# Cartev1.net
KiCad netlist of a schematic drawn in EAGLE
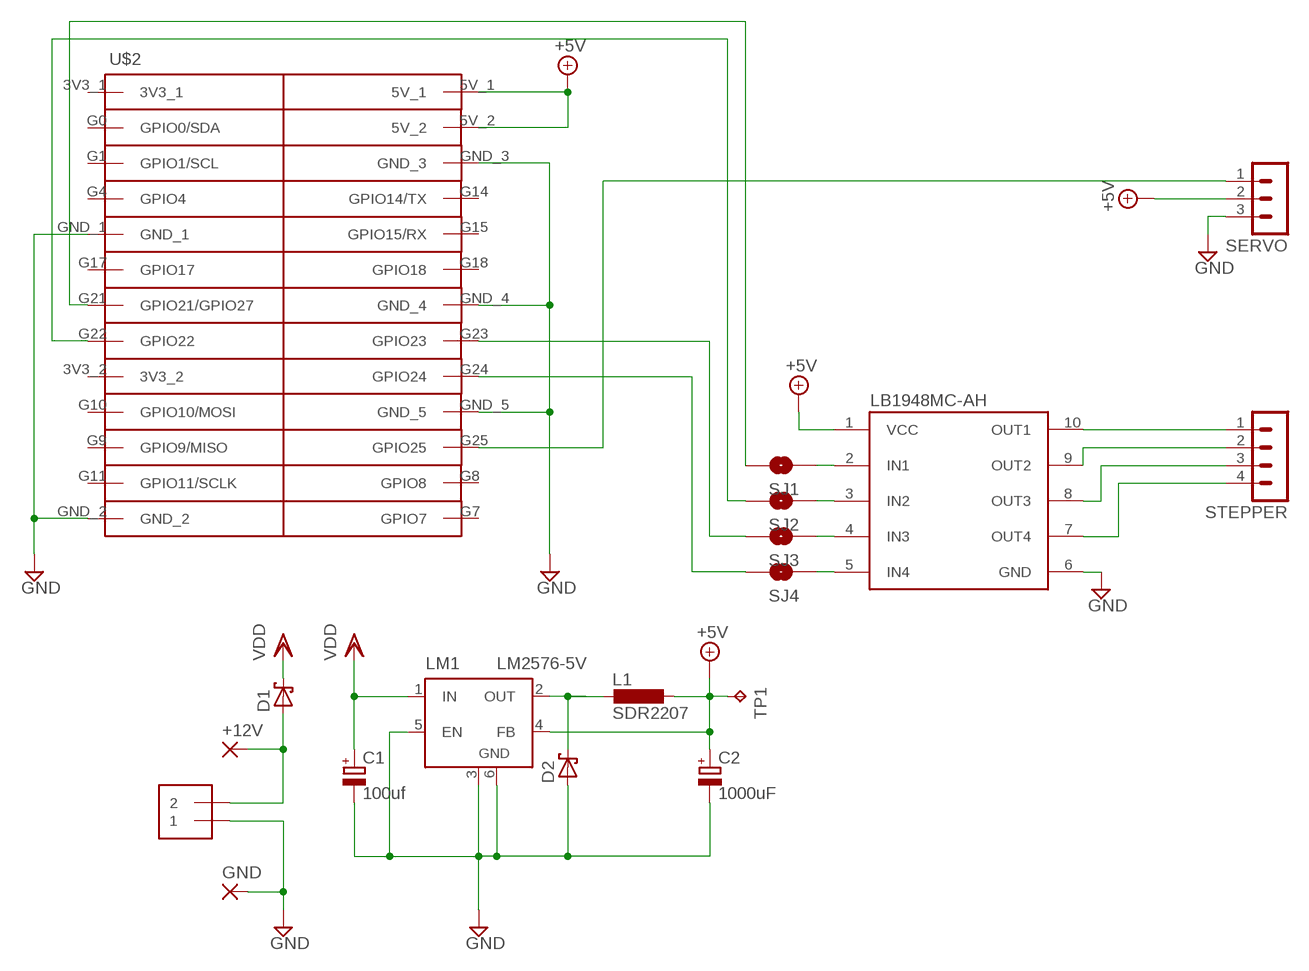
[diagram p0: schematic, sheet 1]

(export (version "E")
  (design (tool "Eeschema 10.0.6"))
  (components
    (comp (ref "+12V")
      (value "3,81/1,4")
      (footprint "eagle-import:3,81_1,4")
      (libsource (lib "eagle-import") (part "3,81/1,4"))
    )
    (comp (ref "C1")
      (value "100uf")
      (footprint "eagle-import:PANASONIC_E")
      (libsource (lib "eagle-import") (part "CPOL-EUE"))
    )
    (comp (ref "C2")
      (value "1000uF")
      (footprint "eagle-import:PANASONIC_G")
      (libsource (lib "eagle-import") (part "CPOL-EUG"))
    )
    (comp (ref "D1")
      (value "SCHOTTKY-DIODESMC")
      (footprint "eagle-import:SMC")
      (libsource (lib "eagle-import") (part "SCHOTTKY-DIODESMC"))
    )
    (comp (ref "D2")
      (value "SCHOTTKY-DIODESMC")
      (footprint "eagle-import:SMC")
      (libsource (lib "eagle-import") (part "SCHOTTKY-DIODESMC"))
    )
    (comp (ref "GND")
      (value "3,81/1,4")
      (footprint "eagle-import:3,81_1,4")
      (libsource (lib "eagle-import") (part "3,81/1,4"))
    )
    (comp (ref "J1")
      (value "1X2-3.5MM")
      (footprint "eagle-import:3.5MMTERM")
      (libsource (lib "eagle-import") (part "1X2-3.5MM"))
    )
    (comp (ref "L1")
      (value "SDR2207")
      (footprint "eagle-import:SM")
      (libsource (lib "eagle-import") (part "SDR2207"))
    )
    (comp (ref "LB1948MC-AH")
      (value "LB1948MC-AH")
      (footprint "eagle-import:SOIC-10")
      (libsource (lib "eagle-import") (part "LB1948MC-AH"))
    )
    (comp (ref "LM1")
      (value "LM2576-5V")
      (footprint "eagle-import:TO263-5")
      (libsource (lib "eagle-import") (part "LM2596S"))
    )
    (comp (ref "SERVO")
      (value "MA03-1")
      (footprint "eagle-import:MA03-1")
      (libsource (lib "eagle-import") (part "MA03-1"))
    )
    (comp (ref "SJ1")
      (value "SOLDERJUMPERTRACE")
      (footprint "eagle-import:SJ_2S-TRACE")
      (libsource (lib "eagle-import") (part "SOLDERJUMPERTRACE"))
    )
    (comp (ref "SJ2")
      (value "SOLDERJUMPERTRACE")
      (footprint "eagle-import:SJ_2S-TRACE")
      (libsource (lib "eagle-import") (part "SOLDERJUMPERTRACE"))
    )
    (comp (ref "SJ3")
      (value "SOLDERJUMPERTRACE")
      (footprint "eagle-import:SJ_2S-TRACE")
      (libsource (lib "eagle-import") (part "SOLDERJUMPERTRACE"))
    )
    (comp (ref "SJ4")
      (value "SOLDERJUMPERTRACE")
      (footprint "eagle-import:SJ_2S-TRACE")
      (libsource (lib "eagle-import") (part "SOLDERJUMPERTRACE"))
    )
    (comp (ref "STEPPER")
      (value "MA04-1")
      (footprint "eagle-import:MA04-1")
      (libsource (lib "eagle-import") (part "MA04-1"))
    )
    (comp (ref "TP1")
      (value "TPTP10SQ")
      (footprint "eagle-import:TP10SQ")
      (libsource (lib "eagle-import") (part "TPTP10SQ"))
    )
    (comp (ref "U$2")
      (value "CONNECTEUR_RPI")
      (footprint "eagle-import:26PIN")
      (libsource (lib "eagle-import") (part "CONNECTEUR_RPI"))
    )
  )
  (nets
    (net (code "1") (name "+5V") (class "Default")
      (node (ref "C2") (pin "+") (pinfunction "+_+") (pintype "passive"))
      (node (ref "L1") (pin "P$2") (pinfunction "2_P$2") (pintype "passive"))
      (node (ref "LB1948MC-AH") (pin "1") (pinfunction "VCC_1") (pintype "bidirectional"))
      (node (ref "LM1") (pin "4") (pinfunction "FB_4") (pintype "input"))
      (node (ref "SERVO") (pin "2") (pinfunction "2_2") (pintype "passive"))
      (node (ref "TP1") (pin "TP") (pinfunction "TP_TP") (pintype "input"))
      (node (ref "U$2") (pin "5V_1") (pinfunction "5V_1_5V_1") (pintype "bidirectional"))
      (node (ref "U$2") (pin "5V_2") (pinfunction "5V_2_5V_2") (pintype "bidirectional"))
    )
    (net (code "2") (name "GND") (class "Default")
      (node (ref "C1") (pin "-") (pinfunction "-_-") (pintype "passive"))
      (node (ref "C2") (pin "-") (pinfunction "-_-") (pintype "passive"))
      (node (ref "D2") (pin "A") (pinfunction "A_A") (pintype "passive"))
      (node (ref "GND") (pin "1") (pinfunction "P_1") (pintype "passive"))
      (node (ref "J1") (pin "1") (pinfunction "1_1") (pintype "passive"))
      (node (ref "LB1948MC-AH") (pin "6") (pinfunction "GND_6") (pintype "bidirectional"))
      (node (ref "LM1") (pin "3") (pinfunction "GND_3") (pintype "power_in"))
      (node (ref "LM1") (pin "5") (pinfunction "EN_5") (pintype "input"))
      (node (ref "LM1") (pin "6") (pinfunction "GND_6") (pintype "power_in"))
      (node (ref "SERVO") (pin "3") (pinfunction "3_3") (pintype "passive"))
      (node (ref "U$2") (pin "GND_1") (pinfunction "GND_1_GND_1") (pintype "bidirectional"))
      (node (ref "U$2") (pin "GND_2") (pinfunction "GND_2_GND_2") (pintype "bidirectional"))
      (node (ref "U$2") (pin "GND_3") (pinfunction "GND_3_GND_3") (pintype "bidirectional"))
      (node (ref "U$2") (pin "GND_4") (pinfunction "GND_4_GND_4") (pintype "bidirectional"))
      (node (ref "U$2") (pin "GND_5") (pinfunction "GND_5_GND_5") (pintype "bidirectional"))
    )
    (net (code "3") (name "Net-(+12V-P)") (class "Default")
      (node (ref "+12V") (pin "1") (pinfunction "P_1") (pintype "passive"))
      (node (ref "D1") (pin "A") (pinfunction "A_A") (pintype "passive"))
      (node (ref "J1") (pin "2") (pinfunction "2_2") (pintype "passive"))
    )
    (net (code "4") (name "Net-(L1-1)") (class "Default")
      (node (ref "D2") (pin "C") (pinfunction "C_C") (pintype "passive"))
      (node (ref "L1") (pin "P$1") (pinfunction "1_P$1") (pintype "passive"))
      (node (ref "LM1") (pin "2") (pinfunction "OUT_2") (pintype "output"))
    )
    (net (code "5") (name "Net-(LB1948MC-AH-IN1)") (class "Default")
      (node (ref "LB1948MC-AH") (pin "2") (pinfunction "IN1_2") (pintype "bidirectional"))
      (node (ref "SJ1") (pin "1") (pinfunction "1_1") (pintype "passive"))
    )
    (net (code "6") (name "Net-(LB1948MC-AH-IN2)") (class "Default")
      (node (ref "LB1948MC-AH") (pin "3") (pinfunction "IN2_3") (pintype "bidirectional"))
      (node (ref "SJ2") (pin "1") (pinfunction "1_1") (pintype "passive"))
    )
    (net (code "7") (name "Net-(LB1948MC-AH-IN3)") (class "Default")
      (node (ref "LB1948MC-AH") (pin "4") (pinfunction "IN3_4") (pintype "bidirectional"))
      (node (ref "SJ3") (pin "1") (pinfunction "1_1") (pintype "passive"))
    )
    (net (code "8") (name "Net-(LB1948MC-AH-IN4)") (class "Default")
      (node (ref "LB1948MC-AH") (pin "5") (pinfunction "IN4_5") (pintype "bidirectional"))
      (node (ref "SJ4") (pin "1") (pinfunction "1_1") (pintype "passive"))
    )
    (net (code "9") (name "Net-(LB1948MC-AH-OUT1)") (class "Default")
      (node (ref "LB1948MC-AH") (pin "10") (pinfunction "OUT1_10") (pintype "bidirectional"))
      (node (ref "STEPPER") (pin "1") (pinfunction "1_1") (pintype "passive"))
    )
    (net (code "10") (name "Net-(LB1948MC-AH-OUT2)") (class "Default")
      (node (ref "LB1948MC-AH") (pin "9") (pinfunction "OUT2_9") (pintype "bidirectional"))
      (node (ref "STEPPER") (pin "2") (pinfunction "2_2") (pintype "passive"))
    )
    (net (code "11") (name "Net-(LB1948MC-AH-OUT3)") (class "Default")
      (node (ref "LB1948MC-AH") (pin "8") (pinfunction "OUT3_8") (pintype "bidirectional"))
      (node (ref "STEPPER") (pin "3") (pinfunction "3_3") (pintype "passive"))
    )
    (net (code "12") (name "Net-(LB1948MC-AH-OUT4)") (class "Default")
      (node (ref "LB1948MC-AH") (pin "7") (pinfunction "OUT4_7") (pintype "bidirectional"))
      (node (ref "STEPPER") (pin "4") (pinfunction "4_4") (pintype "passive"))
    )
    (net (code "13") (name "Net-(U$2-GPIO21{slash}GPIO27)") (class "Default")
      (node (ref "SJ1") (pin "2") (pinfunction "2_2") (pintype "passive"))
      (node (ref "U$2") (pin "G21") (pinfunction "GPIO21/GPIO27_G21") (pintype "bidirectional"))
    )
    (net (code "14") (name "Net-(U$2-GPIO22)") (class "Default")
      (node (ref "SJ2") (pin "2") (pinfunction "2_2") (pintype "passive"))
      (node (ref "U$2") (pin "G22") (pinfunction "GPIO22_G22") (pintype "bidirectional"))
    )
    (net (code "15") (name "Net-(U$2-GPIO23)") (class "Default")
      (node (ref "SJ3") (pin "2") (pinfunction "2_2") (pintype "passive"))
      (node (ref "U$2") (pin "G23") (pinfunction "GPIO23_G23") (pintype "bidirectional"))
    )
    (net (code "16") (name "Net-(U$2-GPIO24)") (class "Default")
      (node (ref "SJ4") (pin "2") (pinfunction "2_2") (pintype "passive"))
      (node (ref "U$2") (pin "G24") (pinfunction "GPIO24_G24") (pintype "bidirectional"))
    )
    (net (code "17") (name "Net-(U$2-GPIO25)") (class "Default")
      (node (ref "SERVO") (pin "1") (pinfunction "1_1") (pintype "passive"))
      (node (ref "U$2") (pin "G25") (pinfunction "GPIO25_G25") (pintype "bidirectional"))
    )
    (net (code "18") (name "VDD") (class "Default")
      (node (ref "C1") (pin "+") (pinfunction "+_+") (pintype "passive"))
      (node (ref "D1") (pin "C") (pinfunction "C_C") (pintype "passive"))
      (node (ref "LM1") (pin "1") (pinfunction "IN_1") (pintype "input"))
    )
    (net (code "19") (name "unconnected-(U$2-GPIO0{slash}SDA-PadG0)") (class "Default")
      (node (ref "U$2") (pin "G0") (pinfunction "GPIO0/SDA_G0") (pintype "bidirectional"))
    )
    (net (code "20") (name "unconnected-(U$2-GPIO1{slash}SCL-PadG1)") (class "Default")
      (node (ref "U$2") (pin "G1") (pinfunction "GPIO1/SCL_G1") (pintype "bidirectional"))
    )
    (net (code "21") (name "unconnected-(U$2-GPIO4-PadG4)") (class "Default")
      (node (ref "U$2") (pin "G4") (pinfunction "GPIO4_G4") (pintype "bidirectional"))
    )
    (net (code "22") (name "unconnected-(U$2-GPIO7-PadG7)") (class "Default")
      (node (ref "U$2") (pin "G7") (pinfunction "GPIO7_G7") (pintype "bidirectional"))
    )
    (net (code "23") (name "unconnected-(U$2-GPIO8-PadG8)") (class "Default")
      (node (ref "U$2") (pin "G8") (pinfunction "GPIO8_G8") (pintype "bidirectional"))
    )
    (net (code "24") (name "unconnected-(U$2-GPIO9{slash}MISO-PadG9)") (class "Default")
      (node (ref "U$2") (pin "G9") (pinfunction "GPIO9/MISO_G9") (pintype "bidirectional"))
    )
    (net (code "25") (name "unconnected-(U$2-GPIO10{slash}MOSI-PadG10)") (class "Default")
      (node (ref "U$2") (pin "G10") (pinfunction "GPIO10/MOSI_G10") (pintype "bidirectional"))
    )
    (net (code "26") (name "unconnected-(U$2-GPIO11{slash}SCLK-PadG11)") (class "Default")
      (node (ref "U$2") (pin "G11") (pinfunction "GPIO11/SCLK_G11") (pintype "bidirectional"))
    )
    (net (code "27") (name "unconnected-(U$2-GPIO14{slash}TX-PadG14)") (class "Default")
      (node (ref "U$2") (pin "G14") (pinfunction "GPIO14/TX_G14") (pintype "bidirectional"))
    )
    (net (code "28") (name "unconnected-(U$2-GPIO15{slash}RX-PadG15)") (class "Default")
      (node (ref "U$2") (pin "G15") (pinfunction "GPIO15/RX_G15") (pintype "bidirectional"))
    )
    (net (code "29") (name "unconnected-(U$2-GPIO17-PadG17)") (class "Default")
      (node (ref "U$2") (pin "G17") (pinfunction "GPIO17_G17") (pintype "bidirectional"))
    )
    (net (code "30") (name "unconnected-(U$2-GPIO18-PadG18)") (class "Default")
      (node (ref "U$2") (pin "G18") (pinfunction "GPIO18_G18") (pintype "bidirectional"))
    )
    (net (code "31") (name "unconnected-(U$2-Pad3V3_1)") (class "Default")
      (node (ref "U$2") (pin "3V3_1") (pinfunction "3V3_1_3V3_1") (pintype "bidirectional"))
    )
    (net (code "32") (name "unconnected-(U$2-Pad3V3_2)") (class "Default")
      (node (ref "U$2") (pin "3V3_2") (pinfunction "3V3_2_3V3_2") (pintype "bidirectional"))
    )
  )
)
